# charger.net
KiCad netlist of a schematic drawn in EAGLE
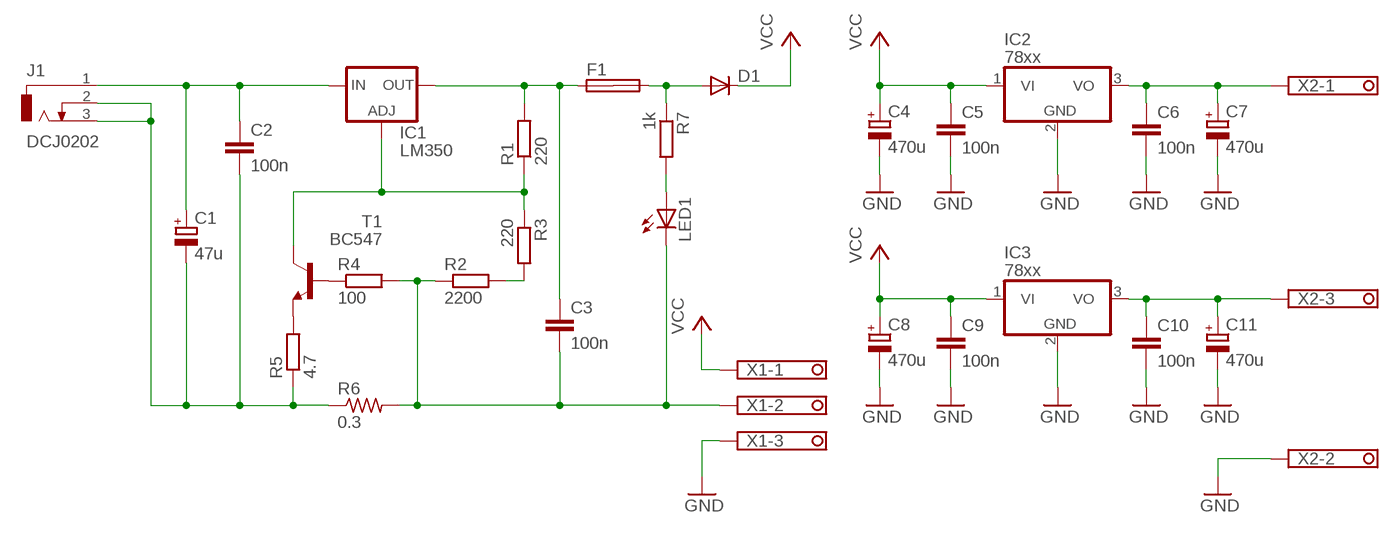
[diagram p0: schematic, sheet 1]

(export (version "E")
  (design (tool "Eeschema 10.0.6"))
  (components
    (comp (ref "C1")
      (value "47u")
      (footprint "eagle-import:E2,5-7")
      (libsource (lib "eagle-import") (part "CPOL-EUE2.5-7"))
    )
    (comp (ref "C2")
      (value "100n")
      (footprint "eagle-import:C050-030X075")
      (libsource (lib "eagle-import") (part "C-EU050-030X075"))
    )
    (comp (ref "C3")
      (value "100n")
      (footprint "eagle-import:C050-030X075")
      (libsource (lib "eagle-import") (part "C-EU050-030X075"))
    )
    (comp (ref "C4")
      (value "470u")
      (footprint "eagle-import:E5-10,5")
      (libsource (lib "eagle-import") (part "CPOL-EUE5-10.5"))
    )
    (comp (ref "C5")
      (value "100n")
      (footprint "eagle-import:C050-030X075")
      (libsource (lib "eagle-import") (part "C-EU050-030X075"))
    )
    (comp (ref "C6")
      (value "100n")
      (footprint "eagle-import:C050-030X075")
      (libsource (lib "eagle-import") (part "C-EU050-030X075"))
    )
    (comp (ref "C7")
      (value "470u")
      (footprint "eagle-import:E5-10,5")
      (libsource (lib "eagle-import") (part "CPOL-EUE5-10.5"))
    )
    (comp (ref "C8")
      (value "470u")
      (footprint "eagle-import:E5-10,5")
      (libsource (lib "eagle-import") (part "CPOL-EUE5-10.5"))
    )
    (comp (ref "C9")
      (value "100n")
      (footprint "eagle-import:C050-030X075")
      (libsource (lib "eagle-import") (part "C-EU050-030X075"))
    )
    (comp (ref "C10")
      (value "100n")
      (footprint "eagle-import:C050-030X075")
      (libsource (lib "eagle-import") (part "C-EU050-030X075"))
    )
    (comp (ref "C11")
      (value "470u")
      (footprint "eagle-import:E5-10,5")
      (libsource (lib "eagle-import") (part "CPOL-EUE5-10.5"))
    )
    (comp (ref "D1")
      (value "SB320")
      (footprint "eagle-import:DO201-15")
      (libsource (lib "eagle-import") (part "SB320"))
    )
    (comp (ref "F1")
      (value "SHK20L")
      (footprint "eagle-import:SHK20L")
      (libsource (lib "eagle-import") (part "SHK20L"))
    )
    (comp (ref "IC1")
      (value "LM350")
      (footprint "eagle-import:317TS")
      (libsource (lib "eagle-import") (part "LM317TS"))
    )
    (comp (ref "IC2")
      (value "78xx")
      (footprint "eagle-import:TO220V")
      (libsource (lib "eagle-import") (part "78TV05"))
    )
    (comp (ref "IC3")
      (value "78xx")
      (footprint "eagle-import:TO220V")
      (libsource (lib "eagle-import") (part "78TV05"))
    )
    (comp (ref "J1")
      (value "DCJ0202")
      (footprint "eagle-import:DCJ0202")
      (libsource (lib "eagle-import") (part "DCJ0202"))
    )
    (comp (ref "LED1")
      (value "LED5MM")
      (footprint "eagle-import:LED5MM")
      (libsource (lib "eagle-import") (part "LED5MM"))
    )
    (comp (ref "R1")
      (value "220")
      (footprint "eagle-import:0207_10")
      (libsource (lib "eagle-import") (part "R-EU_0207/10"))
    )
    (comp (ref "R2")
      (value "2200")
      (footprint "eagle-import:0207_10")
      (libsource (lib "eagle-import") (part "R-EU_0207/10"))
    )
    (comp (ref "R3")
      (value "220")
      (footprint "eagle-import:0207_10")
      (libsource (lib "eagle-import") (part "R-EU_0207/10"))
    )
    (comp (ref "R4")
      (value "100")
      (footprint "eagle-import:0207_10")
      (libsource (lib "eagle-import") (part "R-EU_0207/10"))
    )
    (comp (ref "R5")
      (value "4.7")
      (footprint "eagle-import:0207_10")
      (libsource (lib "eagle-import") (part "R-EU_0207/10"))
    )
    (comp (ref "R6")
      (value "0.3")
      (footprint "eagle-import:0617_22")
      (libsource (lib "eagle-import") (part "R-US_0617/22"))
    )
    (comp (ref "R7")
      (value "1k")
      (footprint "eagle-import:0207_10")
      (libsource (lib "eagle-import") (part "R-EU_0207/10"))
    )
    (comp (ref "T1")
      (value "BC547")
      (footprint "eagle-import:TO92")
      (libsource (lib "eagle-import") (part "BC547"))
    )
    (comp (ref "X1")
      (value "1751251")
      (footprint "eagle-import:1751251")
      (libsource (lib "eagle-import") (part "1751251"))
    )
    (comp (ref "X2")
      (value "1751251")
      (footprint "eagle-import:1751251")
      (libsource (lib "eagle-import") (part "1751251"))
    )
  )
  (nets
    (net (code "1") (name "GND") (class "Default")
      (node (ref "C10") (pin "2") (pinfunction "2_2") (pintype "passive"))
      (node (ref "C11") (pin "-") (pinfunction "-_-") (pintype "passive"))
      (node (ref "C4") (pin "-") (pinfunction "-_-") (pintype "passive"))
      (node (ref "C5") (pin "2") (pinfunction "2_2") (pintype "passive"))
      (node (ref "C6") (pin "2") (pinfunction "2_2") (pintype "passive"))
      (node (ref "C7") (pin "-") (pinfunction "-_-") (pintype "passive"))
      (node (ref "C8") (pin "-") (pinfunction "-_-") (pintype "passive"))
      (node (ref "C9") (pin "2") (pinfunction "2_2") (pintype "passive"))
      (node (ref "IC2") (pin "2") (pinfunction "GND_2") (pintype "passive"))
      (node (ref "IC3") (pin "2") (pinfunction "GND_2") (pintype "passive"))
      (node (ref "X1") (pin "3") (pinfunction "K_3") (pintype "passive"))
      (node (ref "X2") (pin "2") (pinfunction "K_2") (pintype "passive"))
    )
    (net (code "2") (name "Net-(C1-Pad-)") (class "Default")
      (node (ref "C1") (pin "-") (pinfunction "-_-") (pintype "passive"))
      (node (ref "C2") (pin "2") (pinfunction "2_2") (pintype "passive"))
      (node (ref "J1") (pin "2") (pinfunction "2_2") (pintype "passive"))
      (node (ref "J1") (pin "3") (pinfunction "3_3") (pintype "passive"))
      (node (ref "R5") (pin "1") (pinfunction "1_1") (pintype "passive"))
      (node (ref "R6") (pin "1") (pinfunction "1_1") (pintype "passive"))
    )
    (net (code "3") (name "Net-(D1-PadA)") (class "Default")
      (node (ref "D1") (pin "A") (pinfunction "A_A") (pintype "passive"))
      (node (ref "F1") (pin "2A") (pinfunction "2A_2A") (pintype "passive"))
      (node (ref "R7") (pin "1") (pinfunction "1_1") (pintype "passive"))
    )
    (net (code "4") (name "Net-(IC1-ADJ)") (class "Default")
      (node (ref "IC1") (pin "1") (pinfunction "ADJ_1") (pintype "input"))
      (node (ref "R1") (pin "1") (pinfunction "1_1") (pintype "passive"))
      (node (ref "R3") (pin "1") (pinfunction "1_1") (pintype "passive"))
      (node (ref "T1") (pin "3") (pinfunction "C_3") (pintype "passive"))
    )
    (net (code "5") (name "Net-(IC1-IN)") (class "Default")
      (node (ref "C1") (pin "+") (pinfunction "+_+") (pintype "passive"))
      (node (ref "C2") (pin "1") (pinfunction "1_1") (pintype "passive"))
      (node (ref "IC1") (pin "3") (pinfunction "IN_3") (pintype "input"))
      (node (ref "J1") (pin "1") (pinfunction "1_1") (pintype "passive"))
    )
    (net (code "6") (name "Net-(IC1-OUT)") (class "Default")
      (node (ref "C3") (pin "1") (pinfunction "1_1") (pintype "passive"))
      (node (ref "F1") (pin "1A") (pinfunction "1A_1A") (pintype "passive"))
      (node (ref "IC1") (pin "2") (pinfunction "OUT_2") (pintype "passive"))
      (node (ref "R1") (pin "2") (pinfunction "2_2") (pintype "passive"))
    )
    (net (code "7") (name "Net-(IC2-VO)") (class "Default")
      (node (ref "C6") (pin "1") (pinfunction "1_1") (pintype "passive"))
      (node (ref "C7") (pin "+") (pinfunction "+_+") (pintype "passive"))
      (node (ref "IC2") (pin "3") (pinfunction "VO_3") (pintype "passive"))
      (node (ref "X2") (pin "1") (pinfunction "K_1") (pintype "passive"))
    )
    (net (code "8") (name "Net-(IC3-VO)") (class "Default")
      (node (ref "C10") (pin "1") (pinfunction "1_1") (pintype "passive"))
      (node (ref "C11") (pin "+") (pinfunction "+_+") (pintype "passive"))
      (node (ref "IC3") (pin "3") (pinfunction "VO_3") (pintype "passive"))
      (node (ref "X2") (pin "3") (pinfunction "K_3") (pintype "passive"))
    )
    (net (code "9") (name "Net-(LED1-C)") (class "Default")
      (node (ref "C3") (pin "2") (pinfunction "2_2") (pintype "passive"))
      (node (ref "LED1") (pin "K") (pinfunction "C_K") (pintype "passive"))
      (node (ref "R2") (pin "1") (pinfunction "1_1") (pintype "passive"))
      (node (ref "R4") (pin "2") (pinfunction "2_2") (pintype "passive"))
      (node (ref "R6") (pin "2") (pinfunction "2_2") (pintype "passive"))
      (node (ref "X1") (pin "2") (pinfunction "K_2") (pintype "passive"))
    )
    (net (code "10") (name "Net-(LED1-PadA)") (class "Default")
      (node (ref "LED1") (pin "A") (pinfunction "A_A") (pintype "passive"))
      (node (ref "R7") (pin "2") (pinfunction "2_2") (pintype "passive"))
    )
    (net (code "11") (name "Net-(R2-Pad2)") (class "Default")
      (node (ref "R2") (pin "2") (pinfunction "2_2") (pintype "passive"))
      (node (ref "R3") (pin "2") (pinfunction "2_2") (pintype "passive"))
    )
    (net (code "12") (name "Net-(T1-B)") (class "Default")
      (node (ref "R4") (pin "1") (pinfunction "1_1") (pintype "passive"))
      (node (ref "T1") (pin "2") (pinfunction "B_2") (pintype "passive"))
    )
    (net (code "13") (name "Net-(T1-E)") (class "Default")
      (node (ref "R5") (pin "2") (pinfunction "2_2") (pintype "passive"))
      (node (ref "T1") (pin "1") (pinfunction "E_1") (pintype "passive"))
    )
    (net (code "14") (name "VCC") (class "Default")
      (node (ref "C4") (pin "+") (pinfunction "+_+") (pintype "passive"))
      (node (ref "C5") (pin "1") (pinfunction "1_1") (pintype "passive"))
      (node (ref "C8") (pin "+") (pinfunction "+_+") (pintype "passive"))
      (node (ref "C9") (pin "1") (pinfunction "1_1") (pintype "passive"))
      (node (ref "D1") (pin "C") (pinfunction "C_C") (pintype "passive"))
      (node (ref "IC2") (pin "1") (pinfunction "VI_1") (pintype "input"))
      (node (ref "IC3") (pin "1") (pinfunction "VI_1") (pintype "input"))
      (node (ref "X1") (pin "1") (pinfunction "K_1") (pintype "passive"))
    )
    (net (code "15") (name "unconnected-(F1-Pad1B)") (class "Default")
      (node (ref "F1") (pin "1B") (pinfunction "1B_1B") (pintype "passive"))
    )
    (net (code "16") (name "unconnected-(F1-Pad2B)") (class "Default")
      (node (ref "F1") (pin "2B") (pinfunction "2B_2B") (pintype "passive"))
    )
  )
)
